# BUTTONS.net
KiCad netlist of a schematic drawn in Altium Designer
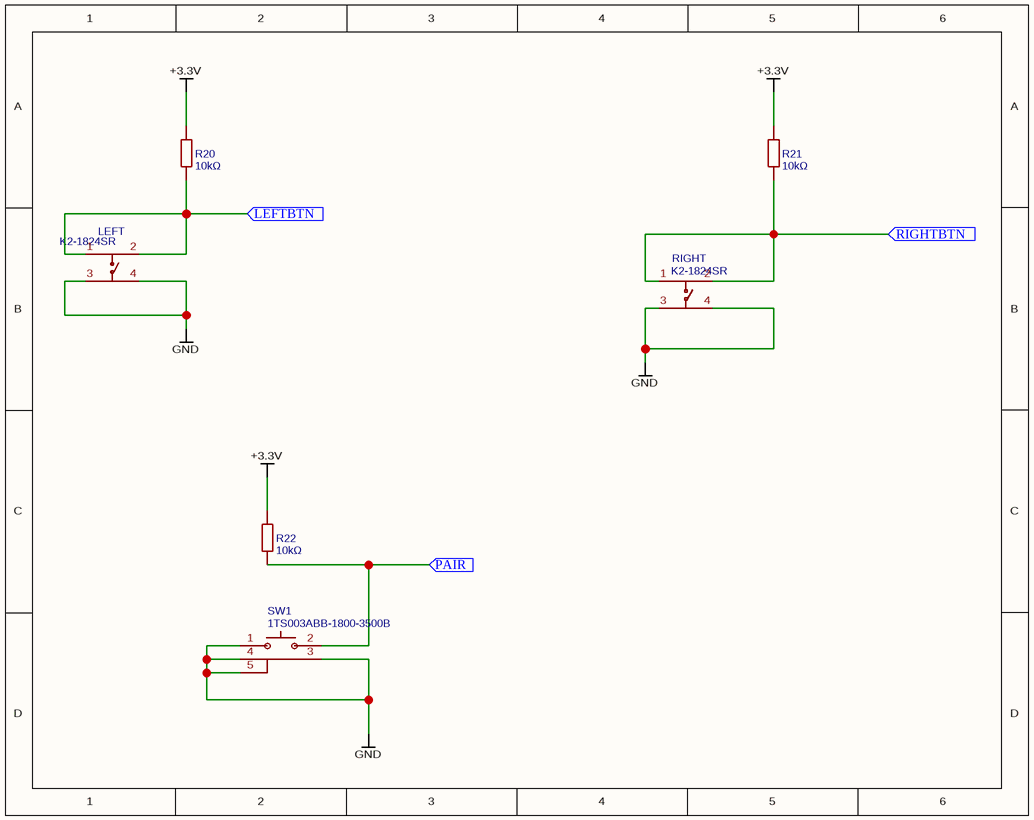
[diagram p0: BUTTONS.schdoc]

(export (version "E")
  (design (tool "Eeschema 10.0.6"))
  (components
    (comp (ref "LEFT")
      (value "K2-1824SR")
      (fields
        (field (name "BOM_MANUFACTURER PART") "K2-1824SR-B4SW-06")
        (field (name "BOM_SUPPLIER PART") "C128938")
        (field (name "CONTRIBUTOR") "LCSC")
      )
      (libsource (lib "altium-import") (part "root_0_K2-1824SR_"))
    )
    (comp (ref "R20")
      (value "10kΩ")
      (fields
        (field (name "BOM_SUPPLIER PART") "C115324")
        (field (name "BOM_MANUFACTURER PART") "RS-03K1002FT")
        (field (name "CONTRIBUTOR") "LCSC")
      )
      (libsource (lib "altium-import") (part "root_1_10kΩ_"))
    )
    (comp (ref "R21")
      (value "10kΩ")
      (fields
        (field (name "BOM_SUPPLIER PART") "C115324")
        (field (name "BOM_MANUFACTURER PART") "RS-03K1002FT")
        (field (name "CONTRIBUTOR") "LCSC")
      )
      (libsource (lib "altium-import") (part "root_1_10kΩ_"))
    )
    (comp (ref "R22")
      (value "10kΩ")
      (fields
        (field (name "BOM_SUPPLIER PART") "C115324")
        (field (name "BOM_MANUFACTURER PART") "RS-03K1002FT")
        (field (name "CONTRIBUTOR") "LCSC")
      )
      (libsource (lib "altium-import") (part "root_1_10kΩ_"))
    )
    (comp (ref "RIGHT")
      (value "K2-1824SR")
      (fields
        (field (name "BOM_MANUFACTURER PART") "K2-1824SR-B4SW-06")
        (field (name "BOM_SUPPLIER PART") "C128938")
        (field (name "CONTRIBUTOR") "LCSC")
      )
      (libsource (lib "altium-import") (part "root_0_K2-1824SR_"))
    )
    (comp (ref "SW1")
      (value "1TS003ABB-1800-3500B")
      (fields (field (name "BOM_SUPPLIER PART") "C319390") (field (name "CONTRIBUTOR") "LCSC"))
      (libsource (lib "altium-import") (part "root_0_1TS003ABB-1800-3500B_"))
    )
  )
  (nets
    (net (code "1") (name "+3.3V") (class "Default")
      (node (ref "R20") (pin "2") (pinfunction "2_2") (pintype "passive"))
      (node (ref "R21") (pin "2") (pinfunction "2_2") (pintype "passive"))
      (node (ref "R22") (pin "2") (pinfunction "2_2") (pintype "passive"))
    )
    (net (code "2") (name "/LEFTBTN") (class "Default")
      (node (ref "LEFT") (pin "1") (pinfunction "1_1") (pintype "passive"))
      (node (ref "LEFT") (pin "2") (pinfunction "2_2") (pintype "passive"))
      (node (ref "R20") (pin "1") (pinfunction "1_1") (pintype "passive"))
    )
    (net (code "3") (name "/PAIR") (class "Default")
      (node (ref "R22") (pin "1") (pinfunction "1_1") (pintype "passive"))
      (node (ref "SW1") (pin "2") (pinfunction "B_2") (pintype "passive"))
    )
    (net (code "4") (name "/RIGHTBTN") (class "Default")
      (node (ref "R21") (pin "1") (pinfunction "1_1") (pintype "passive"))
      (node (ref "RIGHT") (pin "1") (pinfunction "1_1") (pintype "passive"))
      (node (ref "RIGHT") (pin "2") (pinfunction "2_2") (pintype "passive"))
    )
    (net (code "5") (name "GND") (class "Default")
      (node (ref "LEFT") (pin "3") (pinfunction "3_3") (pintype "passive"))
      (node (ref "LEFT") (pin "4") (pinfunction "4_4") (pintype "passive"))
      (node (ref "RIGHT") (pin "3") (pinfunction "3_3") (pintype "passive"))
      (node (ref "RIGHT") (pin "4") (pinfunction "4_4") (pintype "passive"))
      (node (ref "SW1") (pin "1") (pinfunction "A_1") (pintype "passive"))
      (node (ref "SW1") (pin "3") (pinfunction "3_3") (pintype "passive"))
      (node (ref "SW1") (pin "4") (pinfunction "4_4") (pintype "passive"))
      (node (ref "SW1") (pin "5") (pinfunction "5_5") (pintype "passive"))
    )
  )
)
